# source_eagle.net
KiCad netlist of a schematic drawn in EAGLE
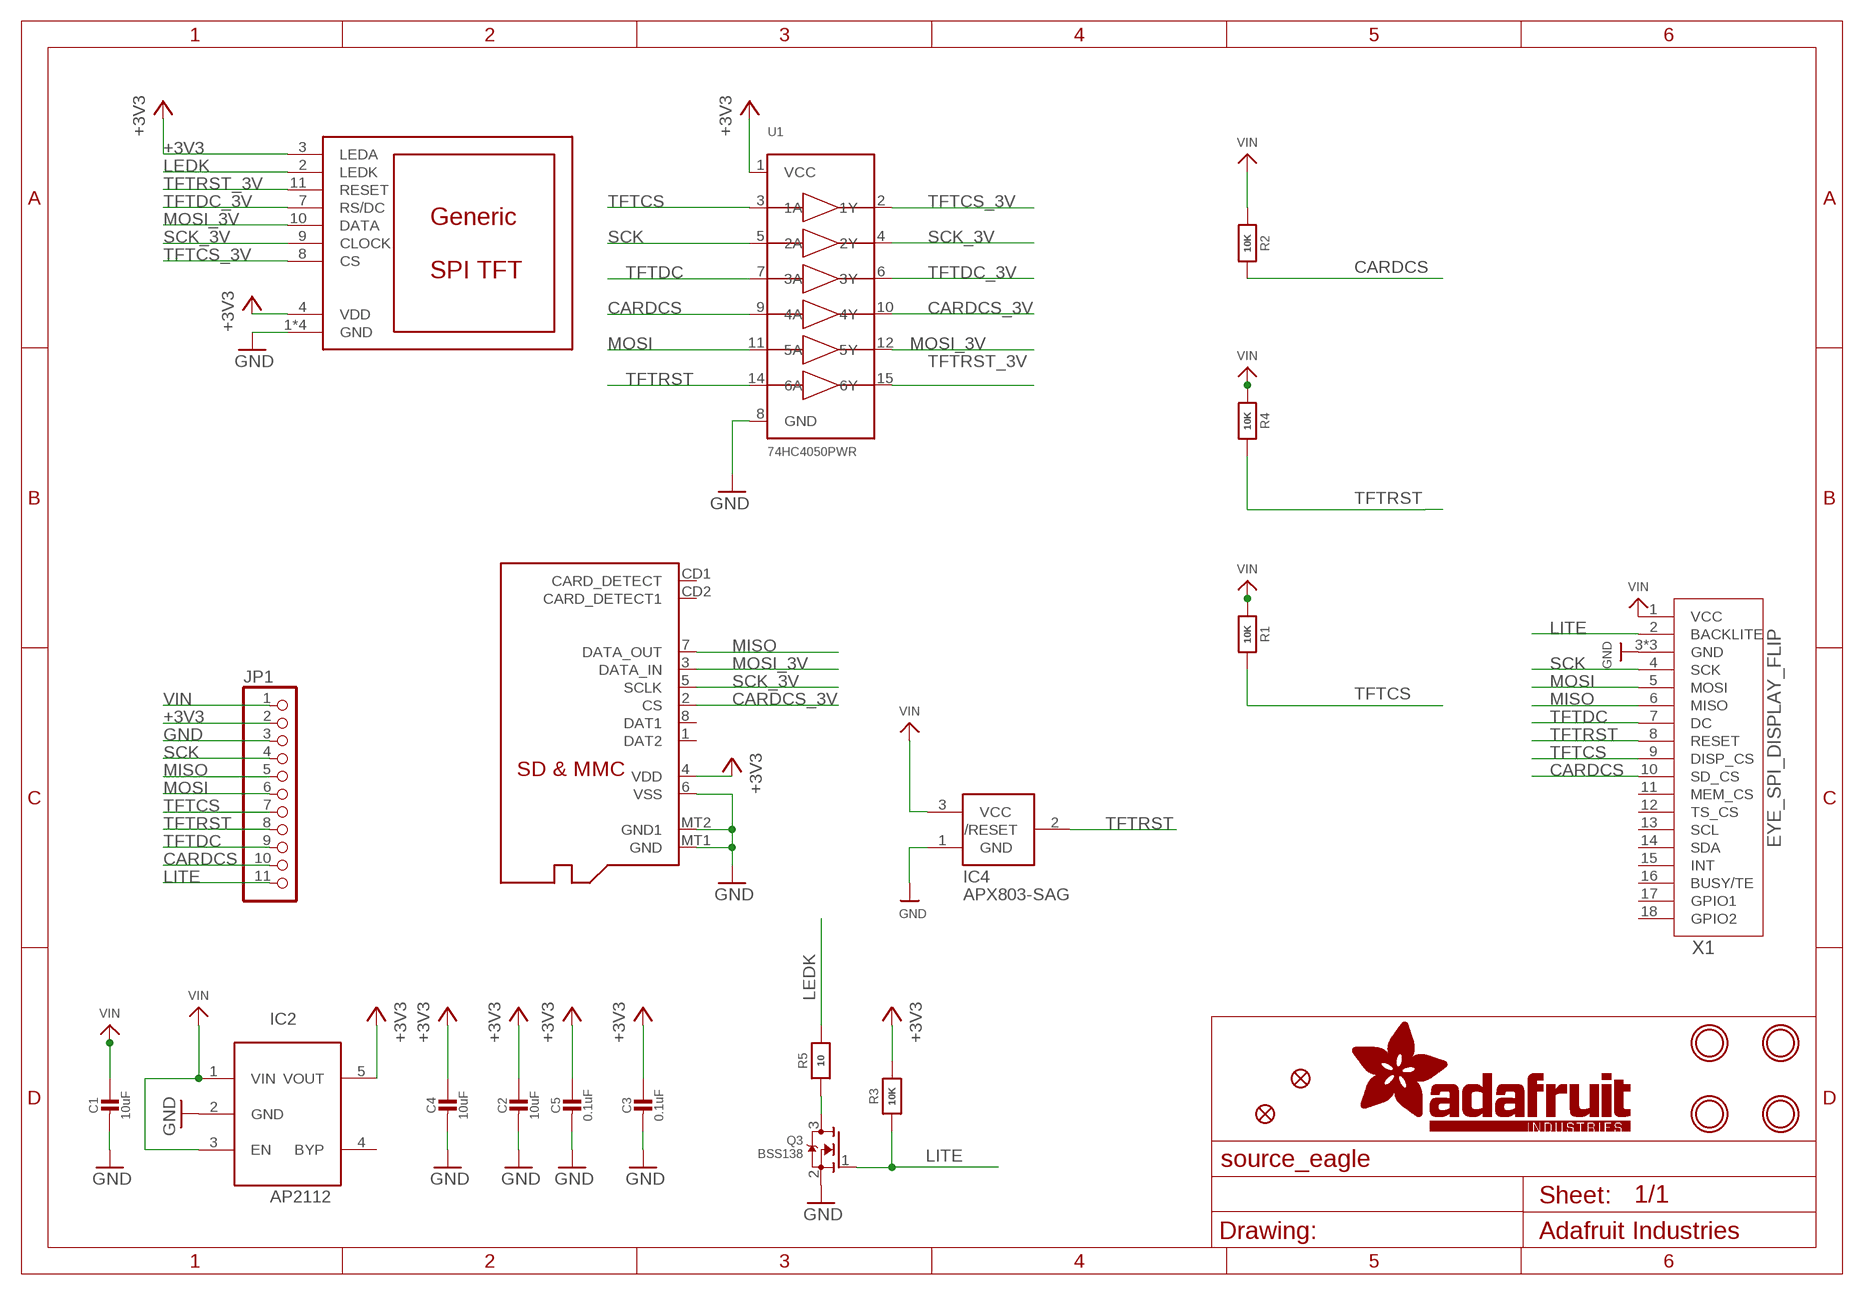
[diagram p0: schematic, sheet 1]

(export (version "E")
  (design (tool "Eeschema 10.0.6"))
  (components
    (comp (ref "C1")
      (value "10uF")
      (footprint "eagle-import:0805-NO")
      (libsource (lib "eagle-import") (part "CAP_CERAMIC0805-NOOUTLINE"))
    )
    (comp (ref "C2")
      (value "10uF")
      (footprint "eagle-import:0805-NO")
      (libsource (lib "eagle-import") (part "CAP_CERAMIC0805-NOOUTLINE"))
    )
    (comp (ref "C3")
      (value "0.1uF")
      (footprint "eagle-import:0603-NO")
      (libsource (lib "eagle-import") (part "CAP_CERAMIC0603_NO"))
    )
    (comp (ref "C4")
      (value "10uF")
      (footprint "eagle-import:0805-NO")
      (libsource (lib "eagle-import") (part "CAP_CERAMIC0805-NOOUTLINE"))
    )
    (comp (ref "C5")
      (value "0.1uF")
      (footprint "eagle-import:0603-NO")
      (libsource (lib "eagle-import") (part "CAP_CERAMIC0603_NO"))
    )
    (comp (ref "DISP1")
      (value "DISP_LCD_GENERIC_SPI_1.69_WRAPUNDER")
      (footprint "eagle-import:TFT_1.69IN_240X280_12P")
      (libsource (lib "eagle-import") (part "DISP_LCD_GENERIC_SPI_1.69_WRAPUNDER"))
    )
    (comp (ref "IC2")
      (value "AP2112")
      (footprint "eagle-import:SOT23-5L")
      (libsource (lib "eagle-import") (part "LP298XS"))
    )
    (comp (ref "IC4")
      (value "APX803-SAG")
      (footprint "eagle-import:SOT23")
      (libsource (lib "eagle-import") (part "AXP083-SAG"))
    )
    (comp (ref "JP1")
      (value "HEADER-1X1176MIL")
      (footprint "eagle-import:1X11_ROUND_76")
      (libsource (lib "eagle-import") (part "HEADER-1X1176MIL"))
    )
    (comp (ref "Q2")
      (value "MICROSD")
      (footprint "eagle-import:MICROSD")
      (libsource (lib "eagle-import") (part "MICROSD"))
    )
    (comp (ref "Q3")
      (value "BSS138")
      (footprint "eagle-import:SOT23-WIDE")
      (libsource (lib "eagle-import") (part "MOSFET-NWIDE"))
    )
    (comp (ref "R1")
      (value "10K")
      (footprint "eagle-import:0603-NO")
      (libsource (lib "eagle-import") (part "RESISTOR_0603_NOOUT"))
    )
    (comp (ref "R2")
      (value "10K")
      (footprint "eagle-import:0603-NO")
      (libsource (lib "eagle-import") (part "RESISTOR_0603_NOOUT"))
    )
    (comp (ref "R3")
      (value "10K")
      (footprint "eagle-import:0603-NO")
      (libsource (lib "eagle-import") (part "RESISTOR_0603_NOOUT"))
    )
    (comp (ref "R4")
      (value "10K")
      (footprint "eagle-import:0603-NO")
      (libsource (lib "eagle-import") (part "RESISTOR_0603_NOOUT"))
    )
    (comp (ref "R5")
      (value "10")
      (footprint "eagle-import:0603-NO")
      (libsource (lib "eagle-import") (part "RESISTOR_0603_NOOUT"))
    )
    (comp (ref "U$4")
      (value "FIDUCIAL_1MM")
      (footprint "eagle-import:FIDUCIAL_1MM")
      (libsource (lib "eagle-import") (part "FIDUCIAL_1MM"))
    )
    (comp (ref "U$5")
      (value "FIDUCIAL_1MM")
      (footprint "eagle-import:FIDUCIAL_1MM")
      (libsource (lib "eagle-import") (part "FIDUCIAL_1MM"))
    )
    (comp (ref "U$7")
      (value "MOUNTINGHOLE2.5")
      (footprint "eagle-import:MOUNTINGHOLE_2.5_PLATED")
      (libsource (lib "eagle-import") (part "MOUNTINGHOLE2.5"))
    )
    (comp (ref "U$8")
      (value "MOUNTINGHOLE2.5")
      (footprint "eagle-import:MOUNTINGHOLE_2.5_PLATED")
      (libsource (lib "eagle-import") (part "MOUNTINGHOLE2.5"))
    )
    (comp (ref "U$9")
      (value "MOUNTINGHOLE2.5")
      (footprint "eagle-import:MOUNTINGHOLE_2.5_PLATED")
      (libsource (lib "eagle-import") (part "MOUNTINGHOLE2.5"))
    )
    (comp (ref "U$10")
      (value "MOUNTINGHOLE2.5")
      (footprint "eagle-import:MOUNTINGHOLE_2.5_PLATED")
      (libsource (lib "eagle-import") (part "MOUNTINGHOLE2.5"))
    )
    (comp (ref "U1")
      (value "74HC4050PWR")
      (footprint "eagle-import:TSSOP16")
      (libsource (lib "eagle-import") (part "74HC4050DTSSOP"))
    )
    (comp (ref "X1")
      (value "EYE_SPI_DISPLAY_FLIP")
      (footprint "eagle-import:EYE_SPI_DISPLAY_BOTCONTACT")
      (libsource (lib "eagle-import") (part "EYE_SPI_DISPLAY_FLIP"))
    )
  )
  (nets
    (net (code "1") (name "+3V3") (class "Default")
      (node (ref "C2") (pin "1") (pinfunction "1_1") (pintype "passive"))
      (node (ref "C3") (pin "1") (pinfunction "1_1") (pintype "passive"))
      (node (ref "C4") (pin "1") (pinfunction "1_1") (pintype "passive"))
      (node (ref "C5") (pin "1") (pinfunction "1_1") (pintype "passive"))
      (node (ref "DISP1") (pin "3") (pinfunction "LEDA_3") (pintype "input"))
      (node (ref "DISP1") (pin "4") (pinfunction "VDD_4") (pintype "power_in"))
      (node (ref "IC2") (pin "5") (pinfunction "VOUT_5") (pintype "bidirectional"))
      (node (ref "JP1") (pin "2") (pinfunction "2_2") (pintype "passive"))
      (node (ref "Q2") (pin "4") (pinfunction "VDD_4") (pintype "power_in"))
      (node (ref "R3") (pin "2") (pinfunction "2_2") (pintype "passive"))
      (node (ref "U1") (pin "1") (pinfunction "VCC_1") (pintype "bidirectional"))
    )
    (net (code "2") (name "/CARDCS") (class "Default")
      (node (ref "JP1") (pin "10") (pinfunction "10_10") (pintype "passive"))
      (node (ref "R2") (pin "1") (pinfunction "1_1") (pintype "passive"))
      (node (ref "U1") (pin "9") (pinfunction "4A_9") (pintype "bidirectional"))
      (node (ref "X1") (pin "10") (pinfunction "SD_CS_10") (pintype "input"))
    )
    (net (code "3") (name "/CARDCS_3V") (class "Default")
      (node (ref "Q2") (pin "2") (pinfunction "CS_2") (pintype "input"))
      (node (ref "U1") (pin "10") (pinfunction "4Y_10") (pintype "bidirectional"))
    )
    (net (code "4") (name "/LEDK") (class "Default")
      (node (ref "DISP1") (pin "2") (pinfunction "LEDK_2") (pintype "input"))
      (node (ref "R5") (pin "2") (pinfunction "2_2") (pintype "passive"))
    )
    (net (code "5") (name "/LITE") (class "Default")
      (node (ref "JP1") (pin "11") (pinfunction "11_11") (pintype "passive"))
      (node (ref "Q3") (pin "1") (pinfunction "G_1") (pintype "bidirectional"))
      (node (ref "R3") (pin "1") (pinfunction "1_1") (pintype "passive"))
      (node (ref "X1") (pin "2") (pinfunction "BACKLITE_2") (pintype "input"))
    )
    (net (code "6") (name "/MISO") (class "Default")
      (node (ref "JP1") (pin "5") (pinfunction "5_5") (pintype "passive"))
      (node (ref "Q2") (pin "7") (pinfunction "DATA_OUT_7") (pintype "output"))
      (node (ref "X1") (pin "6") (pinfunction "MISO_6") (pintype "output"))
    )
    (net (code "7") (name "/MOSI") (class "Default")
      (node (ref "JP1") (pin "6") (pinfunction "6_6") (pintype "passive"))
      (node (ref "U1") (pin "11") (pinfunction "5A_11") (pintype "bidirectional"))
      (node (ref "X1") (pin "5") (pinfunction "MOSI_5") (pintype "input"))
    )
    (net (code "8") (name "/MOSI_3V") (class "Default")
      (node (ref "DISP1") (pin "10") (pinfunction "DATA_10") (pintype "bidirectional"))
      (node (ref "Q2") (pin "3") (pinfunction "DATA_IN_3") (pintype "input"))
      (node (ref "U1") (pin "12") (pinfunction "5Y_12") (pintype "bidirectional"))
    )
    (net (code "9") (name "/SCK") (class "Default")
      (node (ref "JP1") (pin "4") (pinfunction "4_4") (pintype "passive"))
      (node (ref "U1") (pin "5") (pinfunction "2A_5") (pintype "bidirectional"))
      (node (ref "X1") (pin "4") (pinfunction "SCK_4") (pintype "input"))
    )
    (net (code "10") (name "/SCK_3V") (class "Default")
      (node (ref "DISP1") (pin "9") (pinfunction "CLOCK_9") (pintype "input"))
      (node (ref "Q2") (pin "5") (pinfunction "SCLK_5") (pintype "input"))
      (node (ref "U1") (pin "4") (pinfunction "2Y_4") (pintype "bidirectional"))
    )
    (net (code "11") (name "/TFTCS") (class "Default")
      (node (ref "JP1") (pin "7") (pinfunction "7_7") (pintype "passive"))
      (node (ref "R1") (pin "1") (pinfunction "1_1") (pintype "passive"))
      (node (ref "U1") (pin "3") (pinfunction "1A_3") (pintype "bidirectional"))
      (node (ref "X1") (pin "9") (pinfunction "DISP_CS_9") (pintype "input"))
    )
    (net (code "12") (name "/TFTCS_3V") (class "Default")
      (node (ref "DISP1") (pin "8") (pinfunction "CS_8") (pintype "input"))
      (node (ref "U1") (pin "2") (pinfunction "1Y_2") (pintype "bidirectional"))
    )
    (net (code "13") (name "/TFTDC") (class "Default")
      (node (ref "JP1") (pin "9") (pinfunction "9_9") (pintype "passive"))
      (node (ref "U1") (pin "7") (pinfunction "3A_7") (pintype "bidirectional"))
      (node (ref "X1") (pin "7") (pinfunction "DC_7") (pintype "input"))
    )
    (net (code "14") (name "/TFTDC_3V") (class "Default")
      (node (ref "DISP1") (pin "7") (pinfunction "RS/DC_7") (pintype "input"))
      (node (ref "U1") (pin "6") (pinfunction "3Y_6") (pintype "bidirectional"))
    )
    (net (code "15") (name "/TFTRST") (class "Default")
      (node (ref "IC4") (pin "2") (pinfunction "/RESET_2") (pintype "output"))
      (node (ref "JP1") (pin "8") (pinfunction "8_8") (pintype "passive"))
      (node (ref "R4") (pin "1") (pinfunction "1_1") (pintype "passive"))
      (node (ref "U1") (pin "14") (pinfunction "6A_14") (pintype "bidirectional"))
      (node (ref "X1") (pin "8") (pinfunction "RESET_8") (pintype "input"))
    )
    (net (code "16") (name "/TFTRST_3V") (class "Default")
      (node (ref "DISP1") (pin "11") (pinfunction "RESET_11") (pintype "input"))
      (node (ref "U1") (pin "15") (pinfunction "6Y_15") (pintype "bidirectional"))
    )
    (net (code "17") (name "GND") (class "Default")
      (node (ref "C1") (pin "2") (pinfunction "2_2") (pintype "passive"))
      (node (ref "C2") (pin "2") (pinfunction "2_2") (pintype "passive"))
      (node (ref "C3") (pin "2") (pinfunction "2_2") (pintype "passive"))
      (node (ref "C4") (pin "2") (pinfunction "2_2") (pintype "passive"))
      (node (ref "C5") (pin "2") (pinfunction "2_2") (pintype "passive"))
      (node (ref "DISP1") (pin "1") (pinfunction "GND_1") (pintype "power_in"))
      (node (ref "DISP1") (pin "12") (pinfunction "GND_12") (pintype "power_in"))
      (node (ref "DISP1") (pin "5") (pinfunction "GND_5") (pintype "power_in"))
      (node (ref "DISP1") (pin "6") (pinfunction "GND_6") (pintype "power_in"))
      (node (ref "IC2") (pin "2") (pinfunction "GND_2") (pintype "bidirectional"))
      (node (ref "IC4") (pin "1") (pinfunction "GND_1") (pintype "power_in"))
      (node (ref "JP1") (pin "3") (pinfunction "3_3") (pintype "passive"))
      (node (ref "Q2") (pin "6") (pinfunction "VSS_6") (pintype "power_in"))
      (node (ref "Q2") (pin "MT1") (pinfunction "GND_MT1") (pintype "power_in"))
      (node (ref "Q2") (pin "MT2") (pinfunction "GND1_MT2") (pintype "power_in"))
      (node (ref "Q3") (pin "2") (pinfunction "S_2") (pintype "bidirectional"))
      (node (ref "U1") (pin "8") (pinfunction "GND_8") (pintype "bidirectional"))
      (node (ref "X1") (pin "3") (pinfunction "GND_3") (pintype "power_in"))
      (node (ref "X1") (pin "SUPPORT1") (pinfunction "GND_SUPPORT1") (pintype "power_in"))
      (node (ref "X1") (pin "SUPPORT2") (pinfunction "GND_SUPPORT2") (pintype "power_in"))
    )
    (net (code "18") (name "Net-(Q3-D)") (class "Default")
      (node (ref "Q3") (pin "3") (pinfunction "D_3") (pintype "bidirectional"))
      (node (ref "R5") (pin "1") (pinfunction "1_1") (pintype "passive"))
    )
    (net (code "19") (name "VIN") (class "Default")
      (node (ref "C1") (pin "1") (pinfunction "1_1") (pintype "passive"))
      (node (ref "IC2") (pin "1") (pinfunction "VIN_1") (pintype "bidirectional"))
      (node (ref "IC2") (pin "3") (pinfunction "EN_3") (pintype "bidirectional"))
      (node (ref "IC4") (pin "3") (pinfunction "VCC_3") (pintype "power_in"))
      (node (ref "JP1") (pin "1") (pinfunction "1_1") (pintype "passive"))
      (node (ref "R1") (pin "2") (pinfunction "2_2") (pintype "passive"))
      (node (ref "R2") (pin "2") (pinfunction "2_2") (pintype "passive"))
      (node (ref "R4") (pin "2") (pinfunction "2_2") (pintype "passive"))
      (node (ref "X1") (pin "1") (pinfunction "VCC_1") (pintype "power_in"))
    )
    (net (code "20") (name "unconnected-(IC2-BYP-Pad4)") (class "Default")
      (node (ref "IC2") (pin "4") (pinfunction "BYP_4") (pintype "bidirectional"))
    )
    (net (code "21") (name "unconnected-(Q2-CARD_DETECT-PadCD1)") (class "Default")
      (node (ref "Q2") (pin "CD1") (pinfunction "CARD_DETECT_CD1") (pintype "passive"))
    )
    (net (code "22") (name "unconnected-(Q2-CARD_DETECT1-PadCD2)") (class "Default")
      (node (ref "Q2") (pin "CD2") (pinfunction "CARD_DETECT1_CD2") (pintype "passive"))
    )
    (net (code "23") (name "unconnected-(Q2-DAT1-Pad8)") (class "Default")
      (node (ref "Q2") (pin "8") (pinfunction "DAT1_8") (pintype "bidirectional"))
    )
    (net (code "24") (name "unconnected-(Q2-DAT2-Pad1)") (class "Default")
      (node (ref "Q2") (pin "1") (pinfunction "DAT2_1") (pintype "bidirectional"))
    )
    (net (code "25") (name "unconnected-(X1-BUSY{slash}TE-Pad16)") (class "Default")
      (node (ref "X1") (pin "16") (pinfunction "BUSY/TE_16") (pintype "output"))
    )
    (net (code "26") (name "unconnected-(X1-GPIO1-Pad17)") (class "Default")
      (node (ref "X1") (pin "17") (pinfunction "GPIO1_17") (pintype "passive"))
    )
    (net (code "27") (name "unconnected-(X1-GPIO2-Pad18)") (class "Default")
      (node (ref "X1") (pin "18") (pinfunction "GPIO2_18") (pintype "passive"))
    )
    (net (code "28") (name "unconnected-(X1-INT-Pad15)") (class "Default")
      (node (ref "X1") (pin "15") (pinfunction "INT_15") (pintype "output"))
    )
    (net (code "29") (name "unconnected-(X1-MEM_CS-Pad11)") (class "Default")
      (node (ref "X1") (pin "11") (pinfunction "MEM_CS_11") (pintype "input"))
    )
    (net (code "30") (name "unconnected-(X1-SCL-Pad13)") (class "Default")
      (node (ref "X1") (pin "13") (pinfunction "SCL_13") (pintype "input"))
    )
    (net (code "31") (name "unconnected-(X1-SDA-Pad14)") (class "Default")
      (node (ref "X1") (pin "14") (pinfunction "SDA_14") (pintype "bidirectional"))
    )
    (net (code "32") (name "unconnected-(X1-TS_CS-Pad12)") (class "Default")
      (node (ref "X1") (pin "12") (pinfunction "TS_CS_12") (pintype "input"))
    )
  )
)
